# FuncGen_ST.net
KiCad netlist of a schematic drawn in Altium Designer
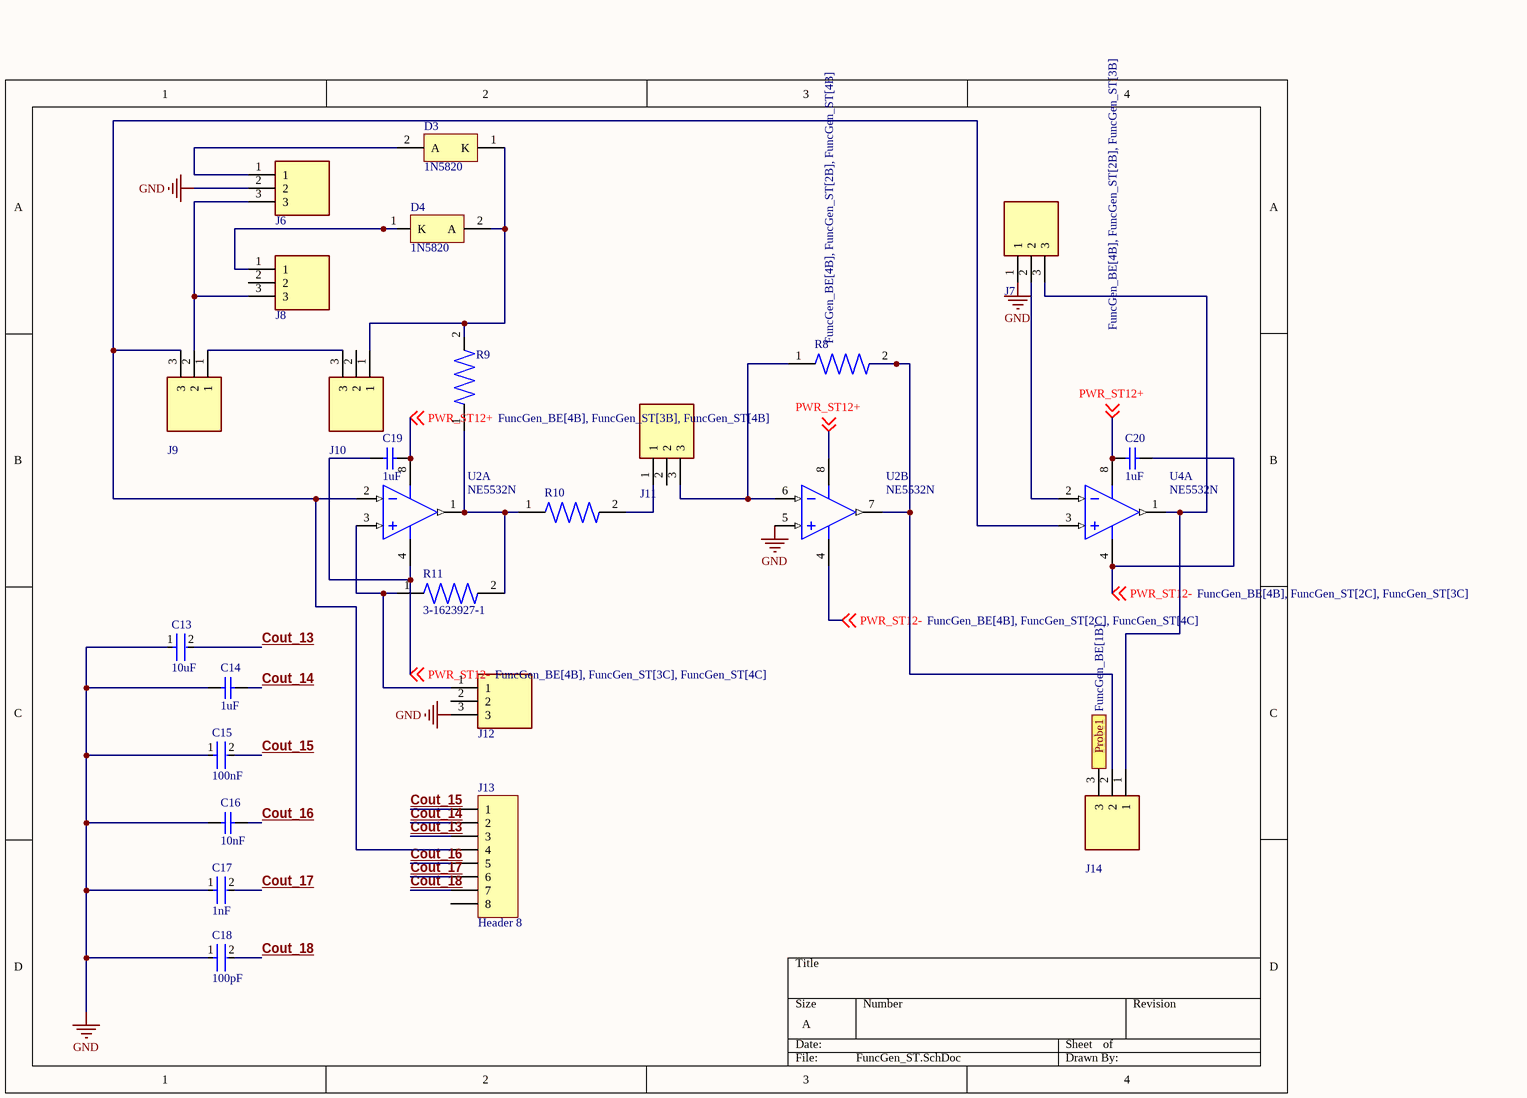
[diagram p0: FuncGen_ST.SchDoc]

(export (version "E")
  (design (tool "Eeschema 10.0.6"))
  (components
    (comp (ref "C13")
      (value "10uF")
      (footprint "FP-RCE3M1-MFG")
      (description "Cap Ceramic 10uF 25V X7R ±10% Radial 5mm +125°C Automotive Ammo Pack")
      (fields (field (name "TOLERANCE") "10%"))
      (libsource (lib "Altium Content Vault") (part "02cd4be3c70576c341d710602a673aa"))
    )
    (comp (ref "C14")
      (value "1uF")
      (footprint "KEMT-C330C105M5U5TA")
      (description "Ceramic Capacitor, 1 uF, +/- 20%, 50 V, -10 to 85 degC, 2-Pin THD, RoHS, Bulk")
      (fields (field (name "TOLERANCE") "±20%") (field (name "MANUFACTURER") "Kemet"))
      (libsource (lib "Altium Content Vault") (part "CAP-NP-2"))
    )
    (comp (ref "C15")
      (value "100nF")
      (footprint "FP-C322C104K5R5TA-MFG")
      (description "CAP CER 0.1UF 50V X7R RADIAL")
      (fields (field (name "TOLERANCE") "10%") (field (name "VOLTAGE") "50V"))
      (libsource (lib "Altium Content Vault") (part "b4654b650e69147ec39a6b967a45e02"))
    )
    (comp (ref "C16")
      (value "10nF")
      (footprint "KEMT-C315-THT-2")
      (description "Capacitor, Ceramic, 0.01 uF, +/- 10%, 100 V, X7R, -55 to 125 degC, 2-Pin THD, RoHS, Bulk")
      (libsource (lib "Altium Content Vault") (part "CAP-NP-2"))
    )
    (comp (ref "C17")
      (value "1nF")
      (footprint "FP-DE6_D7_T7_F7_5_d0_6-0-MFG")
      (description "CAP CER 1000PF 300VAC RADIAL")
      (fields (field (name "TOLERANCE") "20%"))
      (libsource (lib "Altium Content Vault") (part "7bc8f122f62ff4f5a687363419e79e3"))
    )
    (comp (ref "C18")
      (value "100pF")
      (footprint "FP-RCE0K1-MFG")
      (description "Cap Ceramic 100pF 50V C0G ±5% Radial 5mm +125°C Automotive Bulk")
      (fields (field (name "TOLERANCE") "5%"))
      (libsource (lib "Altium Content Vault") (part "b4654b650e69147ec39a6b967a45e02"))
    )
    (comp (ref "C19")
      (value "1uF")
      (footprint "KEMT-C330C105M5U5TA")
      (description "Ceramic Capacitor, 1 uF, +/- 20%, 50 V, -10 to 85 degC, 2-Pin THD, RoHS, Bulk")
      (fields (field (name "TOLERANCE") "±20%") (field (name "MANUFACTURER") "Kemet"))
      (libsource (lib "Altium Content Vault") (part "CAP-NP-2"))
    )
    (comp (ref "C20")
      (value "1uF")
      (footprint "KEMT-C330C105M5U5TA")
      (description "Ceramic Capacitor, 1 uF, +/- 20%, 50 V, -10 to 85 degC, 2-Pin THD, RoHS, Bulk")
      (fields (field (name "TOLERANCE") "±20%") (field (name "MANUFACTURER") "Kemet"))
      (libsource (lib "Altium Content Vault") (part "CAP-NP-2"))
    )
    (comp (ref "D3")
      (value "1N5820")
      (footprint "ONSC-AXIAL_LEAD-2-267-05_V")
      (description "Rectifier, 2-Pin Axial_Lead, Bulk Bag")
      (fields (field (name "MANUFACTURER") "On Semiconductor"))
      (libsource (lib "") (part "ONSC-D-K1A2-2_A_1"))
    )
    (comp (ref "D4")
      (value "1N5820")
      (footprint "ONSC-AXIAL_LEAD-2-267-05_V")
      (description "Rectifier, 2-Pin Axial_Lead, Bulk Bag")
      (fields (field (name "MANUFACTURER") "On Semiconductor"))
      (libsource (lib "Altium Content Vault") (part "ONSC-D-K1A2-2_A"))
    )
    (comp (ref "J6")
      (value "3-644456-3")
      (footprint "TE_3-644456-3")
      (description "MTA-100 3 Position Through-Hole Single Row Straight Wire to Board Header")
      (fields (field (name "MF") "TE Connectivity"))
      (libsource (lib "3-644456-3") (part "3-644456-3"))
    )
    (comp (ref "J7")
      (value "3-644456-3")
      (footprint "TE_3-644456-3")
      (description "MTA-100 3 Position Through-Hole Single Row Straight Wire to Board Header")
      (fields (field (name "MF") "TE Connectivity"))
      (libsource (lib "") (part "3-644456-3_2"))
    )
    (comp (ref "J8")
      (value "3-644456-3")
      (footprint "TE_3-644456-3")
      (description "MTA-100 3 Position Through-Hole Single Row Straight Wire to Board Header")
      (fields (field (name "MF") "TE Connectivity"))
      (libsource (lib "3-644456-3") (part "3-644456-3"))
    )
    (comp (ref "J9")
      (value "3-644456-3")
      (footprint "TE_3-644456-3")
      (description "MTA-100 3 Position Through-Hole Single Row Straight Wire to Board Header")
      (fields (field (name "MF") "TE Connectivity"))
      (libsource (lib "") (part "3-644456-3_1"))
    )
    (comp (ref "J10")
      (value "3-644456-3")
      (footprint "TE_3-644456-3")
      (description "MTA-100 3 Position Through-Hole Single Row Straight Wire to Board Header")
      (fields (field (name "MF") "TE Connectivity"))
      (libsource (lib "") (part "3-644456-3_1"))
    )
    (comp (ref "J11")
      (value "3-644456-3")
      (footprint "TE_3-644456-3")
      (description "MTA-100 3 Position Through-Hole Single Row Straight Wire to Board Header")
      (fields (field (name "MF") "TE Connectivity"))
      (libsource (lib "") (part "3-644456-3_2"))
    )
    (comp (ref "J12")
      (value "3-644456-3")
      (footprint "TE_3-644456-3")
      (description "MTA-100 3 Position Through-Hole Single Row Straight Wire to Board Header")
      (fields (field (name "MF") "TE Connectivity"))
      (libsource (lib "3-644456-3") (part "3-644456-3"))
    )
    (comp (ref "J13")
      (value "Header 8")
      (footprint "HDR1X8")
      (description "Header, 8-Pin")
      (fields (field (name "PUBLISHER") "Altium Limited"))
      (libsource (lib "Miscellaneous Connectors") (part "Header 8"))
    )
    (comp (ref "J14")
      (value "3-644456-3")
      (footprint "TE_3-644456-3")
      (description "MTA-100 3 Position Through-Hole Single Row Straight Wire to Board Header")
      (fields (field (name "MF") "TE Connectivity"))
      (libsource (lib "") (part "3-644456-3_1"))
    )
    (comp (ref "R8")
      (value "3-1623927-1")
      (footprint "RESAD700W45L350D185")
      (description "1 MOhms Â±5% 0.25W, 1/4W Through Hole Resistor Axial - Carbon Film")
      (fields (field (name "MF") "TE Connectivity"))
      (libsource (lib "3-1623927-1") (part "3-1623927-1"))
    )
    (comp (ref "R9")
      (value "3-1623927-1")
      (footprint "RESAD700W45L350D185")
      (description "1 MOhms Â±5% 0.25W, 1/4W Through Hole Resistor Axial - Carbon Film")
      (fields (field (name "MF") "TE Connectivity"))
      (libsource (lib "3-1623927-1") (part "3-1623927-1"))
    )
    (comp (ref "R10")
      (value "3-1623927-1")
      (footprint "RESAD700W45L350D185")
      (description "1 MOhms Â±5% 0.25W, 1/4W Through Hole Resistor Axial - Carbon Film")
      (fields (field (name "MF") "TE Connectivity"))
      (libsource (lib "3-1623927-1") (part "3-1623927-1"))
    )
    (comp (ref "R11")
      (value "3-1623927-1")
      (footprint "RESAD700W45L350D185")
      (description "1 MOhms Â±5% 0.25W, 1/4W Through Hole Resistor Axial - Carbon Film")
      (fields (field (name "MF") "TE Connectivity"))
      (libsource (lib "3-1623927-1") (part "3-1623927-1"))
    )
    (comp (ref "U2")
      (value "NE5532N")
      (footprint "ONSC-PDIP-8-626-05")
      (fields (field (name "MANUFACTURER") "On Semiconductor"))
      (libsource (lib "Altium Content Vault") (part "ONSC-NE5532-PDIP-8-626-05"))
    )
    (comp (ref "U4")
      (value "NE5532N")
      (footprint "ONSC-PDIP-8-626-05")
      (fields (field (name "MANUFACTURER") "On Semiconductor"))
      (libsource (lib "Altium Content Vault") (part "ONSC-NE5532-PDIP-8-626-05"))
    )
  )
  (nets
    (net (code "1") (name "/Cout_13") (class "Default")
      (node (ref "C13") (pin "2") (pinfunction "2_2") (pintype "passive"))
      (node (ref "J13") (pin "3") (pinfunction "3_3") (pintype "passive"))
    )
    (net (code "2") (name "/Cout_14") (class "Default")
      (node (ref "C14") (pin "2") (pinfunction "2_2") (pintype "passive"))
      (node (ref "J13") (pin "2") (pinfunction "2_2") (pintype "passive"))
    )
    (net (code "3") (name "/Cout_15") (class "Default")
      (node (ref "C15") (pin "2") (pinfunction "2_2") (pintype "passive"))
      (node (ref "J13") (pin "1") (pinfunction "1_1") (pintype "passive"))
    )
    (net (code "4") (name "/Cout_16") (class "Default")
      (node (ref "C16") (pin "2") (pinfunction "2_2") (pintype "passive"))
      (node (ref "J13") (pin "5") (pinfunction "5_5") (pintype "passive"))
    )
    (net (code "5") (name "/Cout_17") (class "Default")
      (node (ref "C17") (pin "2") (pinfunction "2_2") (pintype "passive"))
      (node (ref "J13") (pin "6") (pinfunction "6_6") (pintype "passive"))
    )
    (net (code "6") (name "/Cout_18") (class "Default")
      (node (ref "C18") (pin "2") (pinfunction "2_2") (pintype "passive"))
      (node (ref "J13") (pin "7") (pinfunction "7_7") (pintype "passive"))
    )
    (net (code "7") (name "/Probe1") (class "Default")
      (node (ref "J14") (pin "3") (pinfunction "3_3") (pintype "passive"))
    )
    (net (code "8") (name "GND") (class "Default")
      (node (ref "C13") (pin "1") (pinfunction "1_1") (pintype "passive"))
      (node (ref "C14") (pin "1") (pinfunction "1_1") (pintype "passive"))
      (node (ref "C15") (pin "1") (pinfunction "1_1") (pintype "passive"))
      (node (ref "C16") (pin "1") (pinfunction "1_1") (pintype "passive"))
      (node (ref "C17") (pin "1") (pinfunction "1_1") (pintype "passive"))
      (node (ref "C18") (pin "1") (pinfunction "1_1") (pintype "passive"))
      (node (ref "J12") (pin "3") (pinfunction "3_3") (pintype "passive"))
      (node (ref "J6") (pin "2") (pinfunction "2_2") (pintype "passive"))
      (node (ref "J7") (pin "1") (pinfunction "1_1") (pintype "passive"))
      (node (ref "U2") (pin "5") (pinfunction "INB+_5") (pintype "input"))
    )
    (net (code "9") (name "Net-(D3-A)") (class "Default")
      (node (ref "D3") (pin "2") (pinfunction "A_2") (pintype "passive"))
      (node (ref "J6") (pin "1") (pinfunction "1_1") (pintype "passive"))
    )
    (net (code "10") (name "Net-(D3-K)") (class "Default")
      (node (ref "D3") (pin "1") (pinfunction "K_1") (pintype "passive"))
      (node (ref "D4") (pin "2") (pinfunction "A_2") (pintype "passive"))
      (node (ref "J10") (pin "1") (pinfunction "1_1") (pintype "passive"))
      (node (ref "R9") (pin "2") (pinfunction "2_2") (pintype "passive"))
    )
    (net (code "11") (name "Net-(D4-K)") (class "Default")
      (node (ref "D4") (pin "1") (pinfunction "K_1") (pintype "passive"))
      (node (ref "J8") (pin "1") (pinfunction "1_1") (pintype "passive"))
    )
    (net (code "12") (name "Net-(J6-Pad3)") (class "Default")
      (node (ref "J6") (pin "3") (pinfunction "3_3") (pintype "passive"))
      (node (ref "J8") (pin "3") (pinfunction "3_3") (pintype "passive"))
      (node (ref "J9") (pin "2") (pinfunction "2_2") (pintype "passive"))
    )
    (net (code "13") (name "Net-(J10-Pad3)") (class "Default")
      (node (ref "J10") (pin "3") (pinfunction "3_3") (pintype "passive"))
      (node (ref "J9") (pin "1") (pinfunction "1_1") (pintype "passive"))
    )
    (net (code "14") (name "Net-(J11-Pad1)") (class "Default")
      (node (ref "J11") (pin "1") (pinfunction "1_1") (pintype "passive"))
      (node (ref "R10") (pin "2") (pinfunction "2_2") (pintype "passive"))
    )
    (net (code "15") (name "Net-(U2A-INA+)") (class "Default")
      (node (ref "J12") (pin "1") (pinfunction "1_1") (pintype "passive"))
      (node (ref "R11") (pin "1") (pinfunction "1_1") (pintype "passive"))
      (node (ref "U2") (pin "3") (pinfunction "INA+_3") (pintype "input"))
    )
    (net (code "16") (name "Net-(U2A-INA-)") (class "Default")
      (node (ref "J13") (pin "4") (pinfunction "4_4") (pintype "passive"))
      (node (ref "J9") (pin "3") (pinfunction "3_3") (pintype "passive"))
      (node (ref "U2") (pin "2") (pinfunction "INA-_2") (pintype "input"))
      (node (ref "U4") (pin "3") (pinfunction "INA+_3") (pintype "input"))
    )
    (net (code "17") (name "Net-(U2A-OUTA)") (class "Default")
      (node (ref "R10") (pin "1") (pinfunction "1_1") (pintype "passive"))
      (node (ref "R11") (pin "2") (pinfunction "2_2") (pintype "passive"))
      (node (ref "R9") (pin "1") (pinfunction "1_1") (pintype "passive"))
      (node (ref "U2") (pin "1") (pinfunction "OUTA_1") (pintype "output"))
    )
    (net (code "18") (name "Net-(U2B-INB-)") (class "Default")
      (node (ref "J11") (pin "3") (pinfunction "3_3") (pintype "passive"))
      (node (ref "R8") (pin "1") (pinfunction "1_1") (pintype "passive"))
      (node (ref "U2") (pin "6") (pinfunction "INB-_6") (pintype "input"))
    )
    (net (code "19") (name "Net-(U2B-OUTB)") (class "Default")
      (node (ref "J14") (pin "2") (pinfunction "2_2") (pintype "passive"))
      (node (ref "R8") (pin "2") (pinfunction "2_2") (pintype "passive"))
      (node (ref "U2") (pin "7") (pinfunction "OUTB_7") (pintype "output"))
    )
    (net (code "20") (name "Net-(U4A-INA-)") (class "Default")
      (node (ref "J7") (pin "2") (pinfunction "2_2") (pintype "passive"))
      (node (ref "U4") (pin "2") (pinfunction "INA-_2") (pintype "input"))
    )
    (net (code "21") (name "Net-(U4A-OUTA)") (class "Default")
      (node (ref "J14") (pin "1") (pinfunction "1_1") (pintype "passive"))
      (node (ref "J7") (pin "3") (pinfunction "3_3") (pintype "passive"))
      (node (ref "U4") (pin "1") (pinfunction "OUTA_1") (pintype "output"))
    )
    (net (code "22") (name "PWR_ST12+") (class "Default")
      (node (ref "C19") (pin "2") (pinfunction "2_2") (pintype "passive"))
      (node (ref "C20") (pin "1") (pinfunction "1_1") (pintype "passive"))
      (node (ref "U2") (pin "8") (pinfunction "V+_8") (pintype "power_in"))
      (node (ref "U4") (pin "8") (pinfunction "V+_8") (pintype "power_in"))
    )
    (net (code "23") (name "PWR_ST12-") (class "Default")
      (node (ref "C19") (pin "1") (pinfunction "1_1") (pintype "passive"))
      (node (ref "C20") (pin "2") (pinfunction "2_2") (pintype "passive"))
      (node (ref "U2") (pin "4") (pinfunction "V-_4") (pintype "power_in"))
      (node (ref "U4") (pin "4") (pinfunction "V-_4") (pintype "power_in"))
    )
    (net (code "24") (name "unconnected-(J8-Pad2)") (class "Default")
      (node (ref "J8") (pin "2") (pinfunction "2_2") (pintype "passive"))
    )
    (net (code "25") (name "unconnected-(J10-Pad2)") (class "Default")
      (node (ref "J10") (pin "2") (pinfunction "2_2") (pintype "passive"))
    )
    (net (code "26") (name "unconnected-(J11-Pad2)") (class "Default")
      (node (ref "J11") (pin "2") (pinfunction "2_2") (pintype "passive"))
    )
    (net (code "27") (name "unconnected-(J12-Pad2)") (class "Default")
      (node (ref "J12") (pin "2") (pinfunction "2_2") (pintype "passive"))
    )
    (net (code "28") (name "unconnected-(J13-Pad8)") (class "Default")
      (node (ref "J13") (pin "8") (pinfunction "8_8") (pintype "passive"))
    )
  )
)
